# Signal_Outputs.net
KiCad netlist of a schematic drawn in Altium Designer
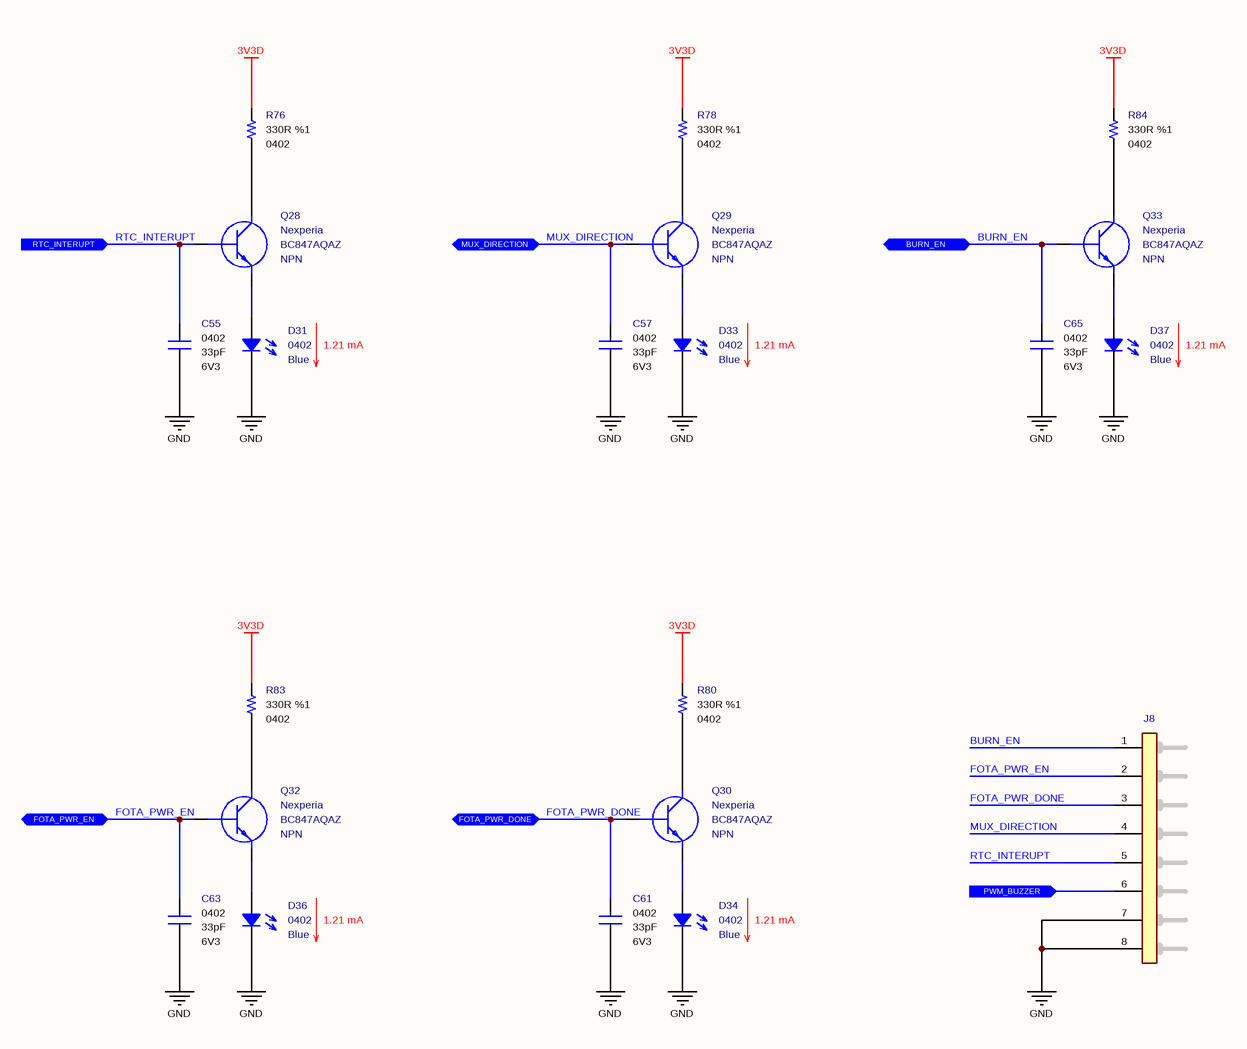
[diagram p0: Signal Outputs.SchDoc]

(export (version "E")
  (design (tool "Eeschema 10.0.6"))
  (components
    (comp (ref "C55")
      (value "33pF")
      (footprint "CAPACITOR_0402")
      (description "Capacitor - 33pF [0402] (Ceramic)")
      (fields
        (field (name "CASE") "0402")
        (field (name "TOLERANCE") "10%")
        (field (name "VOLTAGE") "6V3")
        (field (name "MANUFACTURER PART NUMBER") "C0402C330J9RACAUTO")
      )
      (libsource (lib "Ovoo_Library") (part "Capacitor - 33pF [0402-6V3]"))
    )
    (comp (ref "C57")
      (value "33pF")
      (footprint "CAPACITOR_0402")
      (description "Capacitor - 33pF [0402] (Ceramic)")
      (fields
        (field (name "CASE") "0402")
        (field (name "TOLERANCE") "10%")
        (field (name "VOLTAGE") "6V3")
        (field (name "MANUFACTURER PART NUMBER") "C0402C330J9RACAUTO")
      )
      (libsource (lib "Ovoo_Library") (part "Capacitor - 33pF [0402-6V3]"))
    )
    (comp (ref "C61")
      (value "33pF")
      (footprint "CAPACITOR_0402")
      (description "Capacitor - 33pF [0402] (Ceramic)")
      (fields
        (field (name "CASE") "0402")
        (field (name "TOLERANCE") "10%")
        (field (name "VOLTAGE") "6V3")
        (field (name "MANUFACTURER PART NUMBER") "C0402C330J9RACAUTO")
      )
      (libsource (lib "Ovoo_Library") (part "Capacitor - 33pF [0402-6V3]"))
    )
    (comp (ref "C63")
      (value "33pF")
      (footprint "CAPACITOR_0402")
      (description "Capacitor - 33pF [0402] (Ceramic)")
      (fields
        (field (name "CASE") "0402")
        (field (name "TOLERANCE") "10%")
        (field (name "VOLTAGE") "6V3")
        (field (name "MANUFACTURER PART NUMBER") "C0402C330J9RACAUTO")
      )
      (libsource (lib "Ovoo_Library") (part "Capacitor - 33pF [0402-6V3]"))
    )
    (comp (ref "C65")
      (value "33pF")
      (footprint "CAPACITOR_0402")
      (description "Capacitor - 33pF [0402] (Ceramic)")
      (fields
        (field (name "CASE") "0402")
        (field (name "TOLERANCE") "10%")
        (field (name "VOLTAGE") "6V3")
        (field (name "MANUFACTURER PART NUMBER") "C0402C330J9RACAUTO")
      )
      (libsource (lib "Ovoo_Library") (part "Capacitor - 33pF [0402-6V3]"))
    )
    (comp (ref "D31")
      (value "SMD LED (Blue)")
      (footprint "LED_0402")
      (description "Standard LEDs - SMD PICOLEDTM;BLUE LED; 25M @ 5MA")
      (fields
        (field (name "MANUFACTURER_PART_NUMBER") "SMLP13BC8TT86")
        (field (name "MOUSER_PART_NUMBER") "755-SMLP13BC8TT86")
        (field (name "CASE") "0402")
        (field (name "COLOR") "Blue")
      )
      (libsource (lib "Ovoo_Library") (part "Diode - LED (0402-Blue)"))
    )
    (comp (ref "D33")
      (value "SMD LED (Blue)")
      (footprint "LED_0402")
      (description "Standard LEDs - SMD PICOLEDTM;BLUE LED; 25M @ 5MA")
      (fields
        (field (name "MANUFACTURER_PART_NUMBER") "SMLP13BC8TT86")
        (field (name "MOUSER_PART_NUMBER") "755-SMLP13BC8TT86")
        (field (name "CASE") "0402")
        (field (name "COLOR") "Blue")
      )
      (libsource (lib "Ovoo_Library") (part "Diode - LED (0402-Blue)"))
    )
    (comp (ref "D34")
      (value "SMD LED (Blue)")
      (footprint "LED_0402")
      (description "Standard LEDs - SMD PICOLEDTM;BLUE LED; 25M @ 5MA")
      (fields
        (field (name "MANUFACTURER_PART_NUMBER") "SMLP13BC8TT86")
        (field (name "MOUSER_PART_NUMBER") "755-SMLP13BC8TT86")
        (field (name "CASE") "0402")
        (field (name "COLOR") "Blue")
      )
      (libsource (lib "Ovoo_Library") (part "Diode - LED (0402-Blue)"))
    )
    (comp (ref "D36")
      (value "SMD LED (Blue)")
      (footprint "LED_0402")
      (description "Standard LEDs - SMD PICOLEDTM;BLUE LED; 25M @ 5MA")
      (fields
        (field (name "MANUFACTURER_PART_NUMBER") "SMLP13BC8TT86")
        (field (name "MOUSER_PART_NUMBER") "755-SMLP13BC8TT86")
        (field (name "CASE") "0402")
        (field (name "COLOR") "Blue")
      )
      (libsource (lib "Ovoo_Library") (part "Diode - LED (0402-Blue)"))
    )
    (comp (ref "D37")
      (value "SMD LED (Blue)")
      (footprint "LED_0402")
      (description "Standard LEDs - SMD PICOLEDTM;BLUE LED; 25M @ 5MA")
      (fields
        (field (name "MANUFACTURER_PART_NUMBER") "SMLP13BC8TT86")
        (field (name "MOUSER_PART_NUMBER") "755-SMLP13BC8TT86")
        (field (name "CASE") "0402")
        (field (name "COLOR") "Blue")
      )
      (libsource (lib "Ovoo_Library") (part "Diode - LED (0402-Blue)"))
    )
    (comp (ref "J8")
      (value "2.54 mm Pitch 8P Male Connector")
      (footprint "8P Header")
      (description "Headers & Wire Housings BREAKAWAY HDR VERT 8")
      (fields
        (field (name "MANUFACTURER PART NUMBER") "22-28-4083")
        (field (name "MOUSER PART NUMBER") "538-22-28-4083")
      )
      (libsource (lib "Ovoo_Library") (part "Connector - Male Header 8P (2.54)"))
    )
    (comp (ref "Q28")
      (value "Bipolar NPN Transistors")
      (footprint "SOT1215")
      (description "Bipolar Transistors - BJT BC847AQA/DFN1010D-3/REEL 7\" Q2")
      (fields
        (field (name "MOUSER_PART_NUMBER") "771-BC847AQAZ")
        (field (name "MANUFACTURER_NAME") "Nexperia")
        (field (name "MANUFACTURER_PART_NUMBER") "BC847AQAZ")
        (field (name "POLARITY") "NPN")
      )
      (libsource (lib "Ovoo_Library") (part "Transistor - BC847"))
    )
    (comp (ref "Q29")
      (value "Bipolar NPN Transistors")
      (footprint "SOT1215")
      (description "Bipolar Transistors - BJT BC847AQA/DFN1010D-3/REEL 7\" Q2")
      (fields
        (field (name "MOUSER_PART_NUMBER") "771-BC847AQAZ")
        (field (name "MANUFACTURER_NAME") "Nexperia")
        (field (name "MANUFACTURER_PART_NUMBER") "BC847AQAZ")
        (field (name "POLARITY") "NPN")
      )
      (libsource (lib "Ovoo_Library") (part "Transistor - BC847"))
    )
    (comp (ref "Q30")
      (value "Bipolar NPN Transistors")
      (footprint "SOT1215")
      (description "Bipolar Transistors - BJT BC847AQA/DFN1010D-3/REEL 7\" Q2")
      (fields
        (field (name "MOUSER_PART_NUMBER") "771-BC847AQAZ")
        (field (name "MANUFACTURER_NAME") "Nexperia")
        (field (name "MANUFACTURER_PART_NUMBER") "BC847AQAZ")
        (field (name "POLARITY") "NPN")
      )
      (libsource (lib "Ovoo_Library") (part "Transistor - BC847"))
    )
    (comp (ref "Q32")
      (value "Bipolar NPN Transistors")
      (footprint "SOT1215")
      (description "Bipolar Transistors - BJT BC847AQA/DFN1010D-3/REEL 7\" Q2")
      (fields
        (field (name "MOUSER_PART_NUMBER") "771-BC847AQAZ")
        (field (name "MANUFACTURER_NAME") "Nexperia")
        (field (name "MANUFACTURER_PART_NUMBER") "BC847AQAZ")
        (field (name "POLARITY") "NPN")
      )
      (libsource (lib "Ovoo_Library") (part "Transistor - BC847"))
    )
    (comp (ref "Q33")
      (value "Bipolar NPN Transistors")
      (footprint "SOT1215")
      (description "Bipolar Transistors - BJT BC847AQA/DFN1010D-3/REEL 7\" Q2")
      (fields
        (field (name "MOUSER_PART_NUMBER") "771-BC847AQAZ")
        (field (name "MANUFACTURER_NAME") "Nexperia")
        (field (name "MANUFACTURER_PART_NUMBER") "BC847AQAZ")
        (field (name "POLARITY") "NPN")
      )
      (libsource (lib "Ovoo_Library") (part "Transistor - BC847"))
    )
    (comp (ref "R76")
      (value "330R")
      (footprint "RESISTOR_0402")
      (description "Thick Film Resistors - SMD 1/16 W 330 Ohm 1%")
      (fields
        (field (name "TOLERANCE") "%1")
        (field (name "CASE") "0402")
        (field (name "MANUFACTURER PART NUMBER") "CRCW0402330RFKED")
        (field (name "MOUSER PART NUMBER") "71-CRCW0402-330-E3")
      )
      (libsource (lib "Ovoo_Library") (part "Resistor - 330R"))
    )
    (comp (ref "R78")
      (value "330R")
      (footprint "RESISTOR_0402")
      (description "Thick Film Resistors - SMD 1/16 W 330 Ohm 1%")
      (fields
        (field (name "TOLERANCE") "%1")
        (field (name "CASE") "0402")
        (field (name "MANUFACTURER PART NUMBER") "CRCW0402330RFKED")
        (field (name "MOUSER PART NUMBER") "71-CRCW0402-330-E3")
      )
      (libsource (lib "Ovoo_Library") (part "Resistor - 330R"))
    )
    (comp (ref "R80")
      (value "330R")
      (footprint "RESISTOR_0402")
      (description "Thick Film Resistors - SMD 1/16 W 330 Ohm 1%")
      (fields
        (field (name "TOLERANCE") "%1")
        (field (name "CASE") "0402")
        (field (name "MANUFACTURER PART NUMBER") "CRCW0402330RFKED")
        (field (name "MOUSER PART NUMBER") "71-CRCW0402-330-E3")
      )
      (libsource (lib "Ovoo_Library") (part "Resistor - 330R"))
    )
    (comp (ref "R83")
      (value "330R")
      (footprint "RESISTOR_0402")
      (description "Thick Film Resistors - SMD 1/16 W 330 Ohm 1%")
      (fields
        (field (name "TOLERANCE") "%1")
        (field (name "CASE") "0402")
        (field (name "MANUFACTURER PART NUMBER") "CRCW0402330RFKED")
        (field (name "MOUSER PART NUMBER") "71-CRCW0402-330-E3")
      )
      (libsource (lib "Ovoo_Library") (part "Resistor - 330R"))
    )
    (comp (ref "R84")
      (value "330R")
      (footprint "RESISTOR_0402")
      (description "Thick Film Resistors - SMD 1/16 W 330 Ohm 1%")
      (fields
        (field (name "TOLERANCE") "%1")
        (field (name "CASE") "0402")
        (field (name "MANUFACTURER PART NUMBER") "CRCW0402330RFKED")
        (field (name "MOUSER PART NUMBER") "71-CRCW0402-330-E3")
      )
      (libsource (lib "Ovoo_Library") (part "Resistor - 330R"))
    )
  )
  (nets
    (net (code "1") (name "/BURN_EN") (class "Default")
      (node (ref "C65") (pin "1") (pinfunction "1_1") (pintype "passive"))
      (node (ref "J8") (pin "1") (pinfunction "Pin-1_1") (pintype "passive"))
      (node (ref "Q33") (pin "1") (pinfunction "B_1") (pintype "passive"))
    )
    (net (code "2") (name "/FOTA_PWR_DONE") (class "Default")
      (node (ref "C61") (pin "1") (pinfunction "1_1") (pintype "passive"))
      (node (ref "J8") (pin "3") (pinfunction "Pin-3_3") (pintype "passive"))
      (node (ref "Q30") (pin "1") (pinfunction "B_1") (pintype "passive"))
    )
    (net (code "3") (name "/FOTA_PWR_EN") (class "Default")
      (node (ref "C63") (pin "1") (pinfunction "1_1") (pintype "passive"))
      (node (ref "J8") (pin "2") (pinfunction "Pin-2_2") (pintype "passive"))
      (node (ref "Q32") (pin "1") (pinfunction "B_1") (pintype "passive"))
    )
    (net (code "4") (name "/MUX_DIRECTION") (class "Default")
      (node (ref "C57") (pin "1") (pinfunction "1_1") (pintype "passive"))
      (node (ref "J8") (pin "4") (pinfunction "Pin-4_4") (pintype "passive"))
      (node (ref "Q29") (pin "1") (pinfunction "B_1") (pintype "passive"))
    )
    (net (code "5") (name "/PWM_BUZZER") (class "Default")
      (node (ref "J8") (pin "6") (pinfunction "Pin-6_6") (pintype "passive"))
    )
    (net (code "6") (name "/RTC_INTERUPT") (class "Default")
      (node (ref "C55") (pin "1") (pinfunction "1_1") (pintype "passive"))
      (node (ref "J8") (pin "5") (pinfunction "Pin-5_5") (pintype "passive"))
      (node (ref "Q28") (pin "1") (pinfunction "B_1") (pintype "passive"))
    )
    (net (code "7") (name "3V3D") (class "Default")
      (node (ref "R76") (pin "2") (pinfunction "2_2") (pintype "passive"))
      (node (ref "R78") (pin "2") (pinfunction "2_2") (pintype "passive"))
      (node (ref "R80") (pin "2") (pinfunction "2_2") (pintype "passive"))
      (node (ref "R83") (pin "2") (pinfunction "2_2") (pintype "passive"))
      (node (ref "R84") (pin "2") (pinfunction "2_2") (pintype "passive"))
    )
    (net (code "8") (name "GND") (class "Default")
      (node (ref "C55") (pin "2") (pinfunction "2_2") (pintype "passive"))
      (node (ref "C57") (pin "2") (pinfunction "2_2") (pintype "passive"))
      (node (ref "C61") (pin "2") (pinfunction "2_2") (pintype "passive"))
      (node (ref "C63") (pin "2") (pinfunction "2_2") (pintype "passive"))
      (node (ref "C65") (pin "2") (pinfunction "2_2") (pintype "passive"))
      (node (ref "D31") (pin "1") (pinfunction "1_1") (pintype "passive"))
      (node (ref "D33") (pin "1") (pinfunction "1_1") (pintype "passive"))
      (node (ref "D34") (pin "1") (pinfunction "1_1") (pintype "passive"))
      (node (ref "D36") (pin "1") (pinfunction "1_1") (pintype "passive"))
      (node (ref "D37") (pin "1") (pinfunction "1_1") (pintype "passive"))
      (node (ref "J8") (pin "7") (pinfunction "Pin-7_7") (pintype "passive"))
      (node (ref "J8") (pin "8") (pinfunction "Pin-8_8") (pintype "passive"))
    )
    (net (code "9") (name "Net-(Q28-C)") (class "Default")
      (node (ref "Q28") (pin "3") (pinfunction "C_3") (pintype "passive"))
      (node (ref "R76") (pin "1") (pinfunction "1_1") (pintype "passive"))
    )
    (net (code "10") (name "Net-(Q28-E)") (class "Default")
      (node (ref "D31") (pin "2") (pinfunction "2_2") (pintype "passive"))
      (node (ref "Q28") (pin "2") (pinfunction "E_2") (pintype "passive"))
    )
    (net (code "11") (name "Net-(Q29-C)") (class "Default")
      (node (ref "Q29") (pin "3") (pinfunction "C_3") (pintype "passive"))
      (node (ref "R78") (pin "1") (pinfunction "1_1") (pintype "passive"))
    )
    (net (code "12") (name "Net-(Q29-E)") (class "Default")
      (node (ref "D33") (pin "2") (pinfunction "2_2") (pintype "passive"))
      (node (ref "Q29") (pin "2") (pinfunction "E_2") (pintype "passive"))
    )
    (net (code "13") (name "Net-(Q30-C)") (class "Default")
      (node (ref "Q30") (pin "3") (pinfunction "C_3") (pintype "passive"))
      (node (ref "R80") (pin "1") (pinfunction "1_1") (pintype "passive"))
    )
    (net (code "14") (name "Net-(Q30-E)") (class "Default")
      (node (ref "D34") (pin "2") (pinfunction "2_2") (pintype "passive"))
      (node (ref "Q30") (pin "2") (pinfunction "E_2") (pintype "passive"))
    )
    (net (code "15") (name "Net-(Q32-C)") (class "Default")
      (node (ref "Q32") (pin "3") (pinfunction "C_3") (pintype "passive"))
      (node (ref "R83") (pin "1") (pinfunction "1_1") (pintype "passive"))
    )
    (net (code "16") (name "Net-(Q32-E)") (class "Default")
      (node (ref "D36") (pin "2") (pinfunction "2_2") (pintype "passive"))
      (node (ref "Q32") (pin "2") (pinfunction "E_2") (pintype "passive"))
    )
    (net (code "17") (name "Net-(Q33-C)") (class "Default")
      (node (ref "Q33") (pin "3") (pinfunction "C_3") (pintype "passive"))
      (node (ref "R84") (pin "1") (pinfunction "1_1") (pintype "passive"))
    )
    (net (code "18") (name "Net-(Q33-E)") (class "Default")
      (node (ref "D37") (pin "2") (pinfunction "2_2") (pintype "passive"))
      (node (ref "Q33") (pin "2") (pinfunction "E_2") (pintype "passive"))
    )
  )
)
